# wirelesscontroller.net
KiCad netlist of a schematic drawn in EAGLE
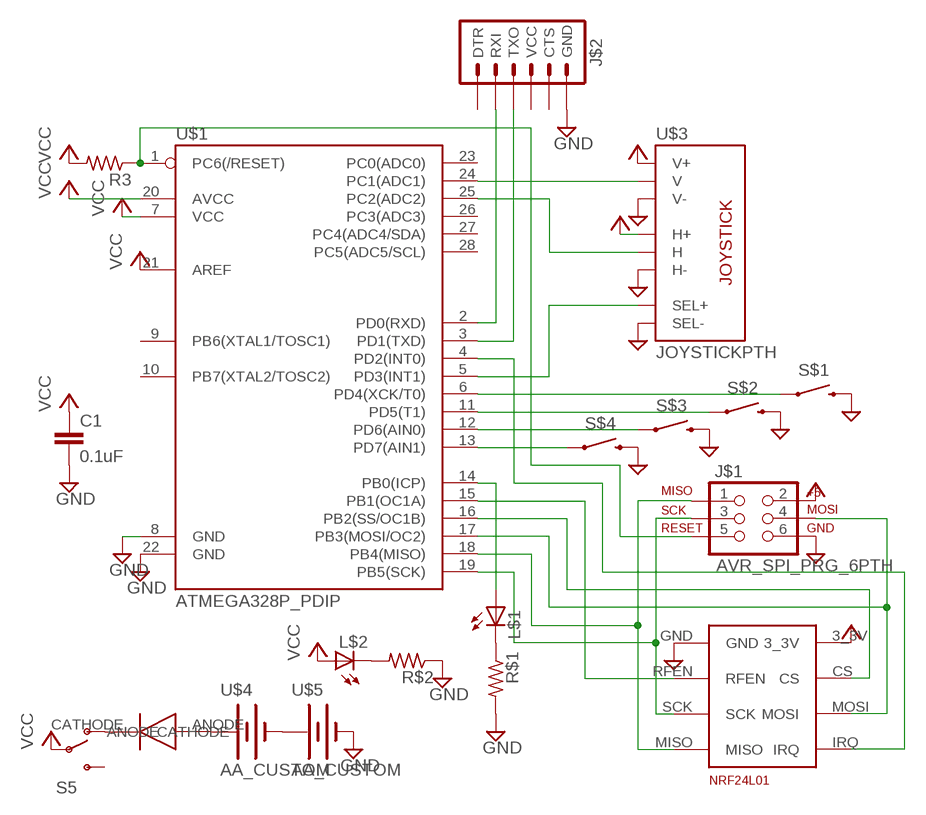
[diagram p0: schematic, sheet 1]

(export (version "E")
  (design (tool "Eeschema 10.0.6"))
  (components
    (comp (ref "C1")
      (value "0.1uF")
      (footprint "eagle-import:0603-CAP")
      (libsource (lib "eagle-import") (part "0.1UF-25V(+80/-20%)(0603)"))
    )
    (comp (ref "D$1")
      (value "DIODE")
      (footprint "eagle-import:R0603")
      (libsource (lib "eagle-import") (part "DIODE"))
    )
    (comp (ref "J$1")
      (value "AVR_SPI_PRG_6PTH")
      (footprint "eagle-import:2X3")
      (libsource (lib "eagle-import") (part "AVR_SPI_PRG_6PTH"))
    )
    (comp (ref "J$2")
      (value "ARDUINO_SERIAL_PROGRAMPTH")
      (footprint "eagle-import:1X06")
      (libsource (lib "eagle-import") (part "ARDUINO_SERIAL_PROGRAMPTH"))
    )
    (comp (ref "L$1")
      (value "LEDCHIPLED_0603")
      (footprint "eagle-import:CHIPLED_0603")
      (libsource (lib "eagle-import") (part "LEDCHIPLED_0603"))
    )
    (comp (ref "L$2")
      (value "LEDCHIPLED_0603")
      (footprint "eagle-import:CHIPLED_0603")
      (libsource (lib "eagle-import") (part "LEDCHIPLED_0603"))
    )
    (comp (ref "R$1")
      (value "R-US_R0603")
      (footprint "eagle-import:R0603")
      (libsource (lib "eagle-import") (part "R-US_R0603"))
    )
    (comp (ref "R$2")
      (value "R-US_R0603")
      (footprint "eagle-import:R0603")
      (libsource (lib "eagle-import") (part "R-US_R0603"))
    )
    (comp (ref "R3")
      (value "R-US_R0603")
      (footprint "eagle-import:R0603")
      (libsource (lib "eagle-import") (part "R-US_R0603"))
    )
    (comp (ref "S$1")
      (value "SWITCH-MOMENTARY-212MM")
      (footprint "eagle-import:TACTILE-PTH-12MM")
      (libsource (lib "eagle-import") (part "SWITCH-MOMENTARY-212MM"))
    )
    (comp (ref "S$2")
      (value "SWITCH-MOMENTARY-212MM")
      (footprint "eagle-import:TACTILE-PTH-12MM")
      (libsource (lib "eagle-import") (part "SWITCH-MOMENTARY-212MM"))
    )
    (comp (ref "S$3")
      (value "SWITCH-MOMENTARY-212MM")
      (footprint "eagle-import:TACTILE-PTH-12MM")
      (libsource (lib "eagle-import") (part "SWITCH-MOMENTARY-212MM"))
    )
    (comp (ref "S$4")
      (value "SWITCH-MOMENTARY-212MM")
      (footprint "eagle-import:TACTILE-PTH-12MM")
      (libsource (lib "eagle-import") (part "SWITCH-MOMENTARY-212MM"))
    )
    (comp (ref "S5")
      (value "SWITCH-SPDTPTH")
      (footprint "eagle-import:SWITCH-SPDT")
      (libsource (lib "eagle-import") (part "SWITCH-SPDTPTH"))
    )
    (comp (ref "U$1")
      (value "ATMEGA328P_PDIP")
      (footprint "eagle-import:DIL28-3")
      (libsource (lib "eagle-import") (part "ATMEGA328P_PDIP"))
    )
    (comp (ref "U$2")
      (value "NRF24L01_BRK")
      (footprint "eagle-import:4X2")
      (libsource (lib "eagle-import") (part "NRF24L01_BRK"))
    )
    (comp (ref "U$3")
      (value "JOYSTICKPTH")
      (footprint "eagle-import:JOYSTICK")
      (libsource (lib "eagle-import") (part "JOYSTICKPTH"))
    )
    (comp (ref "U$4")
      (value "AA_CUSTOM")
      (footprint "eagle-import:AACLIP")
      (libsource (lib "eagle-import") (part "AA_CUSTOM"))
    )
    (comp (ref "U$5")
      (value "AA_CUSTOM")
      (footprint "eagle-import:AACLIP")
      (libsource (lib "eagle-import") (part "AA_CUSTOM"))
    )
  )
  (nets
    (net (code "1") (name "GND") (class "Default")
      (node (ref "C1") (pin "2") (pinfunction "2_2") (pintype "passive"))
      (node (ref "J$1") (pin "6") (pinfunction "6_6") (pintype "passive"))
      (node (ref "J$2") (pin "6") (pinfunction "GND_6") (pintype "passive"))
      (node (ref "R$1") (pin "2") (pinfunction "2_2") (pintype "passive"))
      (node (ref "R$2") (pin "1") (pinfunction "1_1") (pintype "passive"))
      (node (ref "S$1") (pin "3") (pinfunction "2_3") (pintype "passive"))
      (node (ref "S$2") (pin "3") (pinfunction "2_3") (pintype "passive"))
      (node (ref "S$3") (pin "3") (pinfunction "2_3") (pintype "passive"))
      (node (ref "S$4") (pin "3") (pinfunction "2_3") (pintype "passive"))
      (node (ref "U$1") (pin "22") (pinfunction "GND_22") (pintype "bidirectional"))
      (node (ref "U$1") (pin "8") (pinfunction "GND_8") (pintype "bidirectional"))
      (node (ref "U$2") (pin "GND") (pinfunction "GND_GND") (pintype "bidirectional"))
      (node (ref "U$3") (pin "B2A") (pinfunction "SEL-_B2A") (pintype "bidirectional"))
      (node (ref "U$3") (pin "H3") (pinfunction "H-_H3") (pintype "bidirectional"))
      (node (ref "U$3") (pin "V3") (pinfunction "V-_V3") (pintype "bidirectional"))
      (node (ref "U$5") (pin "-") (pinfunction "-_-") (pintype "power_in"))
    )
    (net (code "2") (name "Net-(D$1-PadANODE)") (class "Default")
      (node (ref "D$1") (pin "ANODE") (pinfunction "ANODE_ANODE") (pintype "bidirectional"))
      (node (ref "U$4") (pin "+") (pinfunction "+_+") (pintype "power_in"))
    )
    (net (code "3") (name "Net-(J$2-RXI)") (class "Default")
      (node (ref "J$2") (pin "2") (pinfunction "RXI_2") (pintype "passive"))
      (node (ref "U$1") (pin "2") (pinfunction "PD0(RXD)_2") (pintype "bidirectional"))
    )
    (net (code "4") (name "Net-(J$2-TXO)") (class "Default")
      (node (ref "J$2") (pin "3") (pinfunction "TXO_3") (pintype "passive"))
      (node (ref "U$1") (pin "3") (pinfunction "PD1(TXD)_3") (pintype "bidirectional"))
    )
    (net (code "5") (name "Net-(L$1-PadC)") (class "Default")
      (node (ref "L$1") (pin "C") (pinfunction "C_C") (pintype "passive"))
      (node (ref "R$1") (pin "1") (pinfunction "1_1") (pintype "passive"))
    )
    (net (code "6") (name "Net-(L$2-PadC)") (class "Default")
      (node (ref "L$2") (pin "C") (pinfunction "C_C") (pintype "passive"))
      (node (ref "R$2") (pin "2") (pinfunction "2_2") (pintype "passive"))
    )
    (net (code "7") (name "Net-(S5-O)") (class "Default")
      (node (ref "D$1") (pin "CATHODE") (pinfunction "CATHODE_CATHODE") (pintype "bidirectional"))
      (node (ref "S5") (pin "1") (pinfunction "O_1") (pintype "passive"))
    )
    (net (code "8") (name "Net-(U$1-PB0(ICP))") (class "Default")
      (node (ref "L$1") (pin "A") (pinfunction "A_A") (pintype "passive"))
      (node (ref "U$1") (pin "14") (pinfunction "PB0(ICP)_14") (pintype "bidirectional"))
    )
    (net (code "9") (name "Net-(U$1-PB1(OC1A))") (class "Default")
      (node (ref "U$1") (pin "15") (pinfunction "PB1(OC1A)_15") (pintype "bidirectional"))
      (node (ref "U$2") (pin "RFEN") (pinfunction "RFEN_RFEN") (pintype "bidirectional"))
    )
    (net (code "10") (name "Net-(U$1-PB2(SS{slash}OC1B))") (class "Default")
      (node (ref "U$1") (pin "16") (pinfunction "PB2(SS/OC1B)_16") (pintype "bidirectional"))
      (node (ref "U$2") (pin "CS") (pinfunction "CS_CS") (pintype "bidirectional"))
    )
    (net (code "11") (name "Net-(U$1-PB3(MOSI{slash}OC2))") (class "Default")
      (node (ref "J$1") (pin "4") (pinfunction "4_4") (pintype "passive"))
      (node (ref "U$1") (pin "17") (pinfunction "PB3(MOSI/OC2)_17") (pintype "bidirectional"))
      (node (ref "U$2") (pin "MOSI") (pinfunction "MOSI_MOSI") (pintype "bidirectional"))
    )
    (net (code "12") (name "Net-(U$1-PB4(MISO))") (class "Default")
      (node (ref "J$1") (pin "1") (pinfunction "1_1") (pintype "passive"))
      (node (ref "U$1") (pin "18") (pinfunction "PB4(MISO)_18") (pintype "bidirectional"))
      (node (ref "U$2") (pin "MISO") (pinfunction "MISO_MISO") (pintype "bidirectional"))
    )
    (net (code "13") (name "Net-(U$1-PB5(SCK))") (class "Default")
      (node (ref "J$1") (pin "3") (pinfunction "3_3") (pintype "passive"))
      (node (ref "U$1") (pin "19") (pinfunction "PB5(SCK)_19") (pintype "bidirectional"))
      (node (ref "U$2") (pin "SCK") (pinfunction "SCK_SCK") (pintype "bidirectional"))
    )
    (net (code "14") (name "Net-(U$1-PC1(ADC1))") (class "Default")
      (node (ref "U$1") (pin "24") (pinfunction "PC1(ADC1)_24") (pintype "bidirectional"))
      (node (ref "U$3") (pin "V2") (pinfunction "V_V2") (pintype "bidirectional"))
    )
    (net (code "15") (name "Net-(U$1-PC2(ADC2))") (class "Default")
      (node (ref "U$1") (pin "25") (pinfunction "PC2(ADC2)_25") (pintype "bidirectional"))
      (node (ref "U$3") (pin "H2") (pinfunction "H_H2") (pintype "bidirectional"))
    )
    (net (code "16") (name "Net-(U$1-PC6({slash}RESET))") (class "Default")
      (node (ref "J$1") (pin "5") (pinfunction "5_5") (pintype "passive"))
      (node (ref "R3") (pin "1") (pinfunction "1_1") (pintype "passive"))
      (node (ref "U$1") (pin "1") (pinfunction "PC6(/RESET)_1") (pintype "bidirectional"))
    )
    (net (code "17") (name "Net-(U$1-PD2(INT0))") (class "Default")
      (node (ref "U$1") (pin "4") (pinfunction "PD2(INT0)_4") (pintype "bidirectional"))
      (node (ref "U$2") (pin "IRQ") (pinfunction "IRQ_IRQ") (pintype "bidirectional"))
    )
    (net (code "18") (name "Net-(U$1-PD3(INT1))") (class "Default")
      (node (ref "U$1") (pin "5") (pinfunction "PD3(INT1)_5") (pintype "bidirectional"))
      (node (ref "U$3") (pin "B1A") (pinfunction "SEL+_B1A") (pintype "bidirectional"))
    )
    (net (code "19") (name "Net-(U$1-PD4(XCK{slash}T0))") (class "Default")
      (node (ref "S$1") (pin "1") (pinfunction "1_1") (pintype "passive"))
      (node (ref "U$1") (pin "6") (pinfunction "PD4(XCK/T0)_6") (pintype "bidirectional"))
    )
    (net (code "20") (name "Net-(U$1-PD5(T1))") (class "Default")
      (node (ref "S$2") (pin "1") (pinfunction "1_1") (pintype "passive"))
      (node (ref "U$1") (pin "11") (pinfunction "PD5(T1)_11") (pintype "bidirectional"))
    )
    (net (code "21") (name "Net-(U$1-PD6(AIN0))") (class "Default")
      (node (ref "S$3") (pin "1") (pinfunction "1_1") (pintype "passive"))
      (node (ref "U$1") (pin "12") (pinfunction "PD6(AIN0)_12") (pintype "bidirectional"))
    )
    (net (code "22") (name "Net-(U$1-PD7(AIN1))") (class "Default")
      (node (ref "S$4") (pin "1") (pinfunction "1_1") (pintype "passive"))
      (node (ref "U$1") (pin "13") (pinfunction "PD7(AIN1)_13") (pintype "bidirectional"))
    )
    (net (code "23") (name "Net-(U$4-Pad-)") (class "Default")
      (node (ref "U$4") (pin "-") (pinfunction "-_-") (pintype "power_in"))
      (node (ref "U$5") (pin "+") (pinfunction "+_+") (pintype "power_in"))
    )
    (net (code "24") (name "VCC") (class "Default")
      (node (ref "C1") (pin "1") (pinfunction "1_1") (pintype "passive"))
      (node (ref "J$1") (pin "2") (pinfunction "2_2") (pintype "passive"))
      (node (ref "L$2") (pin "A") (pinfunction "A_A") (pintype "passive"))
      (node (ref "R3") (pin "2") (pinfunction "2_2") (pintype "passive"))
      (node (ref "S5") (pin "2") (pinfunction "P_2") (pintype "passive"))
      (node (ref "U$1") (pin "20") (pinfunction "AVCC_20") (pintype "bidirectional"))
      (node (ref "U$1") (pin "21") (pinfunction "AREF_21") (pintype "bidirectional"))
      (node (ref "U$1") (pin "7") (pinfunction "VCC_7") (pintype "bidirectional"))
      (node (ref "U$2") (pin "3_3V") (pinfunction "3_3V_3_3V") (pintype "bidirectional"))
      (node (ref "U$3") (pin "H1") (pinfunction "H+_H1") (pintype "bidirectional"))
      (node (ref "U$3") (pin "V1") (pinfunction "V+_V1") (pintype "bidirectional"))
    )
    (net (code "25") (name "unconnected-(J$2-CTS-Pad5)") (class "Default")
      (node (ref "J$2") (pin "5") (pinfunction "CTS_5") (pintype "passive"))
    )
    (net (code "26") (name "unconnected-(J$2-DTR-Pad1)") (class "Default")
      (node (ref "J$2") (pin "1") (pinfunction "DTR_1") (pintype "passive"))
    )
    (net (code "27") (name "unconnected-(J$2-VCC-Pad4)") (class "Default")
      (node (ref "J$2") (pin "4") (pinfunction "VCC_4") (pintype "passive"))
    )
    (net (code "28") (name "unconnected-(S5-S-Pad3)") (class "Default")
      (node (ref "S5") (pin "3") (pinfunction "S_3") (pintype "passive"))
    )
    (net (code "29") (name "unconnected-(U$1-PB6(XTAL1{slash}TOSC1)-Pad9)") (class "Default")
      (node (ref "U$1") (pin "9") (pinfunction "PB6(XTAL1/TOSC1)_9") (pintype "bidirectional"))
    )
    (net (code "30") (name "unconnected-(U$1-PB7(XTAL2{slash}TOSC2)-Pad10)") (class "Default")
      (node (ref "U$1") (pin "10") (pinfunction "PB7(XTAL2/TOSC2)_10") (pintype "bidirectional"))
    )
    (net (code "31") (name "unconnected-(U$1-PC0(ADC0)-Pad23)") (class "Default")
      (node (ref "U$1") (pin "23") (pinfunction "PC0(ADC0)_23") (pintype "bidirectional"))
    )
    (net (code "32") (name "unconnected-(U$1-PC3(ADC3)-Pad26)") (class "Default")
      (node (ref "U$1") (pin "26") (pinfunction "PC3(ADC3)_26") (pintype "bidirectional"))
    )
    (net (code "33") (name "unconnected-(U$1-PC4(ADC4{slash}SDA)-Pad27)") (class "Default")
      (node (ref "U$1") (pin "27") (pinfunction "PC4(ADC4/SDA)_27") (pintype "bidirectional"))
    )
    (net (code "34") (name "unconnected-(U$1-PC5(ADC5{slash}SCL)-Pad28)") (class "Default")
      (node (ref "U$1") (pin "28") (pinfunction "PC5(ADC5/SCL)_28") (pintype "bidirectional"))
    )
  )
)
